# Operant-Back.net
KiCad netlist of a schematic drawn in EAGLE
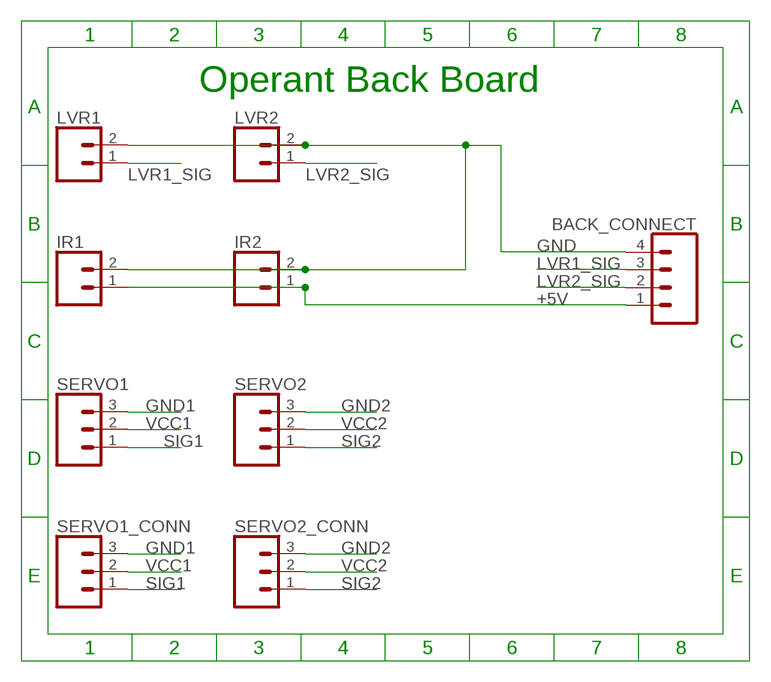
[diagram p0: schematic, sheet 1]

(export (version "E")
  (design (tool "Eeschema 10.0.6"))
  (components
    (comp (ref "BACK_CONNECT")
      (value "CONN_04JST-PTH")
      (footprint "eagle-import:JST-4-PTH")
      (libsource (lib "eagle-import") (part "CONN_04JST-PTH"))
    )
    (comp (ref "IR1")
      (value "CONN_02JST-PTH-2")
      (footprint "eagle-import:JST-2-PTH")
      (libsource (lib "eagle-import") (part "CONN_02JST-PTH-2"))
    )
    (comp (ref "IR2")
      (value "CONN_02JST-PTH-2")
      (footprint "eagle-import:JST-2-PTH")
      (libsource (lib "eagle-import") (part "CONN_02JST-PTH-2"))
    )
    (comp (ref "LVR1")
      (value "CONN_02JST-PTH-2")
      (footprint "eagle-import:JST-2-PTH")
      (libsource (lib "eagle-import") (part "CONN_02JST-PTH-2"))
    )
    (comp (ref "LVR2")
      (value "CONN_02JST-PTH-2")
      (footprint "eagle-import:JST-2-PTH")
      (libsource (lib "eagle-import") (part "CONN_02JST-PTH-2"))
    )
    (comp (ref "SERVO1")
      (value "CONN_03")
      (footprint "eagle-import:1X03")
      (libsource (lib "eagle-import") (part "CONN_03"))
    )
    (comp (ref "SERVO1_CONN")
      (value "CONN_03JST-PTH")
      (footprint "eagle-import:JST-3-PTH")
      (libsource (lib "eagle-import") (part "CONN_03JST-PTH"))
    )
    (comp (ref "SERVO2")
      (value "CONN_03")
      (footprint "eagle-import:1X03")
      (libsource (lib "eagle-import") (part "CONN_03"))
    )
    (comp (ref "SERVO2_CONN")
      (value "CONN_03JST-PTH")
      (footprint "eagle-import:JST-3-PTH")
      (libsource (lib "eagle-import") (part "CONN_03JST-PTH"))
    )
  )
  (nets
    (net (code "1") (name "/+5V") (class "Default")
      (node (ref "BACK_CONNECT") (pin "1") (pinfunction "1_1") (pintype "passive"))
      (node (ref "IR1") (pin "1") (pinfunction "1_1") (pintype "passive"))
      (node (ref "IR2") (pin "1") (pinfunction "1_1") (pintype "passive"))
    )
    (net (code "2") (name "/GND") (class "Default")
      (node (ref "BACK_CONNECT") (pin "4") (pinfunction "4_4") (pintype "passive"))
      (node (ref "IR1") (pin "2") (pinfunction "2_2") (pintype "passive"))
      (node (ref "IR2") (pin "2") (pinfunction "2_2") (pintype "passive"))
      (node (ref "LVR1") (pin "2") (pinfunction "2_2") (pintype "passive"))
      (node (ref "LVR2") (pin "2") (pinfunction "2_2") (pintype "passive"))
    )
    (net (code "3") (name "/GND1") (class "Default")
      (node (ref "SERVO1") (pin "3") (pinfunction "3_3") (pintype "passive"))
      (node (ref "SERVO1_CONN") (pin "3") (pinfunction "3_3") (pintype "passive"))
    )
    (net (code "4") (name "/GND2") (class "Default")
      (node (ref "SERVO2") (pin "3") (pinfunction "3_3") (pintype "passive"))
      (node (ref "SERVO2_CONN") (pin "3") (pinfunction "3_3") (pintype "passive"))
    )
    (net (code "5") (name "/LVR1_SIG") (class "Default")
      (node (ref "BACK_CONNECT") (pin "3") (pinfunction "3_3") (pintype "passive"))
      (node (ref "LVR1") (pin "1") (pinfunction "1_1") (pintype "passive"))
    )
    (net (code "6") (name "/LVR2_SIG") (class "Default")
      (node (ref "BACK_CONNECT") (pin "2") (pinfunction "2_2") (pintype "passive"))
      (node (ref "LVR2") (pin "1") (pinfunction "1_1") (pintype "passive"))
    )
    (net (code "7") (name "/SIG1") (class "Default")
      (node (ref "SERVO1") (pin "1") (pinfunction "1_1") (pintype "passive"))
      (node (ref "SERVO1_CONN") (pin "1") (pinfunction "1_1") (pintype "passive"))
    )
    (net (code "8") (name "/SIG2") (class "Default")
      (node (ref "SERVO2") (pin "1") (pinfunction "1_1") (pintype "passive"))
      (node (ref "SERVO2_CONN") (pin "1") (pinfunction "1_1") (pintype "passive"))
    )
    (net (code "9") (name "/VCC1") (class "Default")
      (node (ref "SERVO1") (pin "2") (pinfunction "2_2") (pintype "passive"))
      (node (ref "SERVO1_CONN") (pin "2") (pinfunction "2_2") (pintype "passive"))
    )
    (net (code "10") (name "/VCC2") (class "Default")
      (node (ref "SERVO2") (pin "2") (pinfunction "2_2") (pintype "passive"))
      (node (ref "SERVO2_CONN") (pin "2") (pinfunction "2_2") (pintype "passive"))
    )
  )
)
